# 7SegmentDisplay.net
KiCad netlist of a schematic drawn in EAGLE
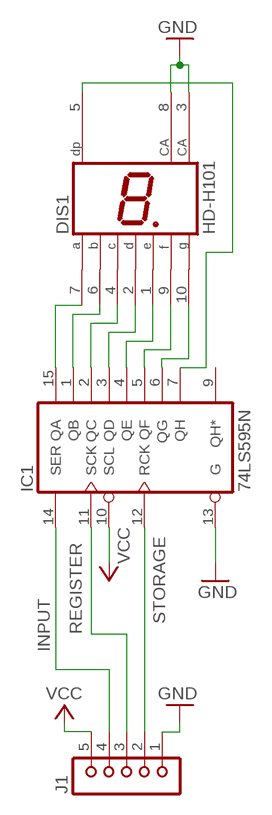
[diagram p0: schematic, sheet 1]

(export (version "E")
  (design (tool "Eeschema 10.0.6"))
  (components
    (comp (ref "DIS1")
      (value "HD-H101")
      (footprint "eagle-import:HDSP-M")
      (libsource (lib "eagle-import") (part "HD-H101"))
    )
    (comp (ref "IC1")
      (value "74LS595N")
      (footprint "eagle-import:DIL16")
      (libsource (lib "eagle-import") (part "74595NLS"))
    )
    (comp (ref "J1")
      (value "JU05")
      (footprint "eagle-import:JU05")
      (libsource (lib "eagle-import") (part "JU05"))
    )
  )
  (nets
    (net (code "1") (name "/INPUT") (class "Default")
      (node (ref "IC1") (pin "14") (pinfunction "SER_14") (pintype "input"))
      (node (ref "J1") (pin "4") (pinfunction "4_4") (pintype "passive"))
    )
    (net (code "2") (name "/REGISTER") (class "Default")
      (node (ref "IC1") (pin "11") (pinfunction "SCK_11") (pintype "input"))
      (node (ref "J1") (pin "3") (pinfunction "3_3") (pintype "passive"))
    )
    (net (code "3") (name "/STORAGE") (class "Default")
      (node (ref "IC1") (pin "12") (pinfunction "RCK_12") (pintype "input"))
      (node (ref "J1") (pin "2") (pinfunction "2_2") (pintype "passive"))
    )
    (net (code "4") (name "GND") (class "Default")
      (node (ref "DIS1") (pin "3") (pinfunction "CA_3") (pintype "passive"))
      (node (ref "DIS1") (pin "8") (pinfunction "CA_8") (pintype "passive"))
      (node (ref "IC1") (pin "13") (pinfunction "G_13") (pintype "input"))
      (node (ref "J1") (pin "1") (pinfunction "1_1") (pintype "passive"))
    )
    (net (code "5") (name "Net-(DIS1-A)") (class "Default")
      (node (ref "DIS1") (pin "7") (pinfunction "A_7") (pintype "passive"))
      (node (ref "IC1") (pin "15") (pinfunction "QA_15") (pintype "tri_state"))
    )
    (net (code "6") (name "Net-(DIS1-B)") (class "Default")
      (node (ref "DIS1") (pin "6") (pinfunction "B_6") (pintype "passive"))
      (node (ref "IC1") (pin "1") (pinfunction "QB_1") (pintype "tri_state"))
    )
    (net (code "7") (name "Net-(DIS1-C)") (class "Default")
      (node (ref "DIS1") (pin "4") (pinfunction "C_4") (pintype "passive"))
      (node (ref "IC1") (pin "2") (pinfunction "QC_2") (pintype "tri_state"))
    )
    (net (code "8") (name "Net-(DIS1-D)") (class "Default")
      (node (ref "DIS1") (pin "2") (pinfunction "D_2") (pintype "passive"))
      (node (ref "IC1") (pin "3") (pinfunction "QD_3") (pintype "tri_state"))
    )
    (net (code "9") (name "Net-(DIS1-DP)") (class "Default")
      (node (ref "DIS1") (pin "5") (pinfunction "DP_5") (pintype "passive"))
      (node (ref "IC1") (pin "7") (pinfunction "QH_7") (pintype "tri_state"))
    )
    (net (code "10") (name "Net-(DIS1-E)") (class "Default")
      (node (ref "DIS1") (pin "1") (pinfunction "E_1") (pintype "passive"))
      (node (ref "IC1") (pin "4") (pinfunction "QE_4") (pintype "tri_state"))
    )
    (net (code "11") (name "Net-(DIS1-F)") (class "Default")
      (node (ref "DIS1") (pin "9") (pinfunction "F_9") (pintype "passive"))
      (node (ref "IC1") (pin "5") (pinfunction "QF_5") (pintype "tri_state"))
    )
    (net (code "12") (name "Net-(DIS1-G)") (class "Default")
      (node (ref "DIS1") (pin "10") (pinfunction "G_10") (pintype "passive"))
      (node (ref "IC1") (pin "6") (pinfunction "QG_6") (pintype "tri_state"))
    )
    (net (code "13") (name "VCC") (class "Default")
      (node (ref "IC1") (pin "10") (pinfunction "SCL_10") (pintype "input"))
      (node (ref "J1") (pin "5") (pinfunction "5_5") (pintype "passive"))
    )
    (net (code "14") (name "unconnected-(IC1A-QH*-Pad9)") (class "Default")
      (node (ref "IC1") (pin "9") (pinfunction "QH*_9") (pintype "tri_state"))
    )
  )
)
